# esd_project.net
KiCad netlist of a schematic drawn in Altium Designer
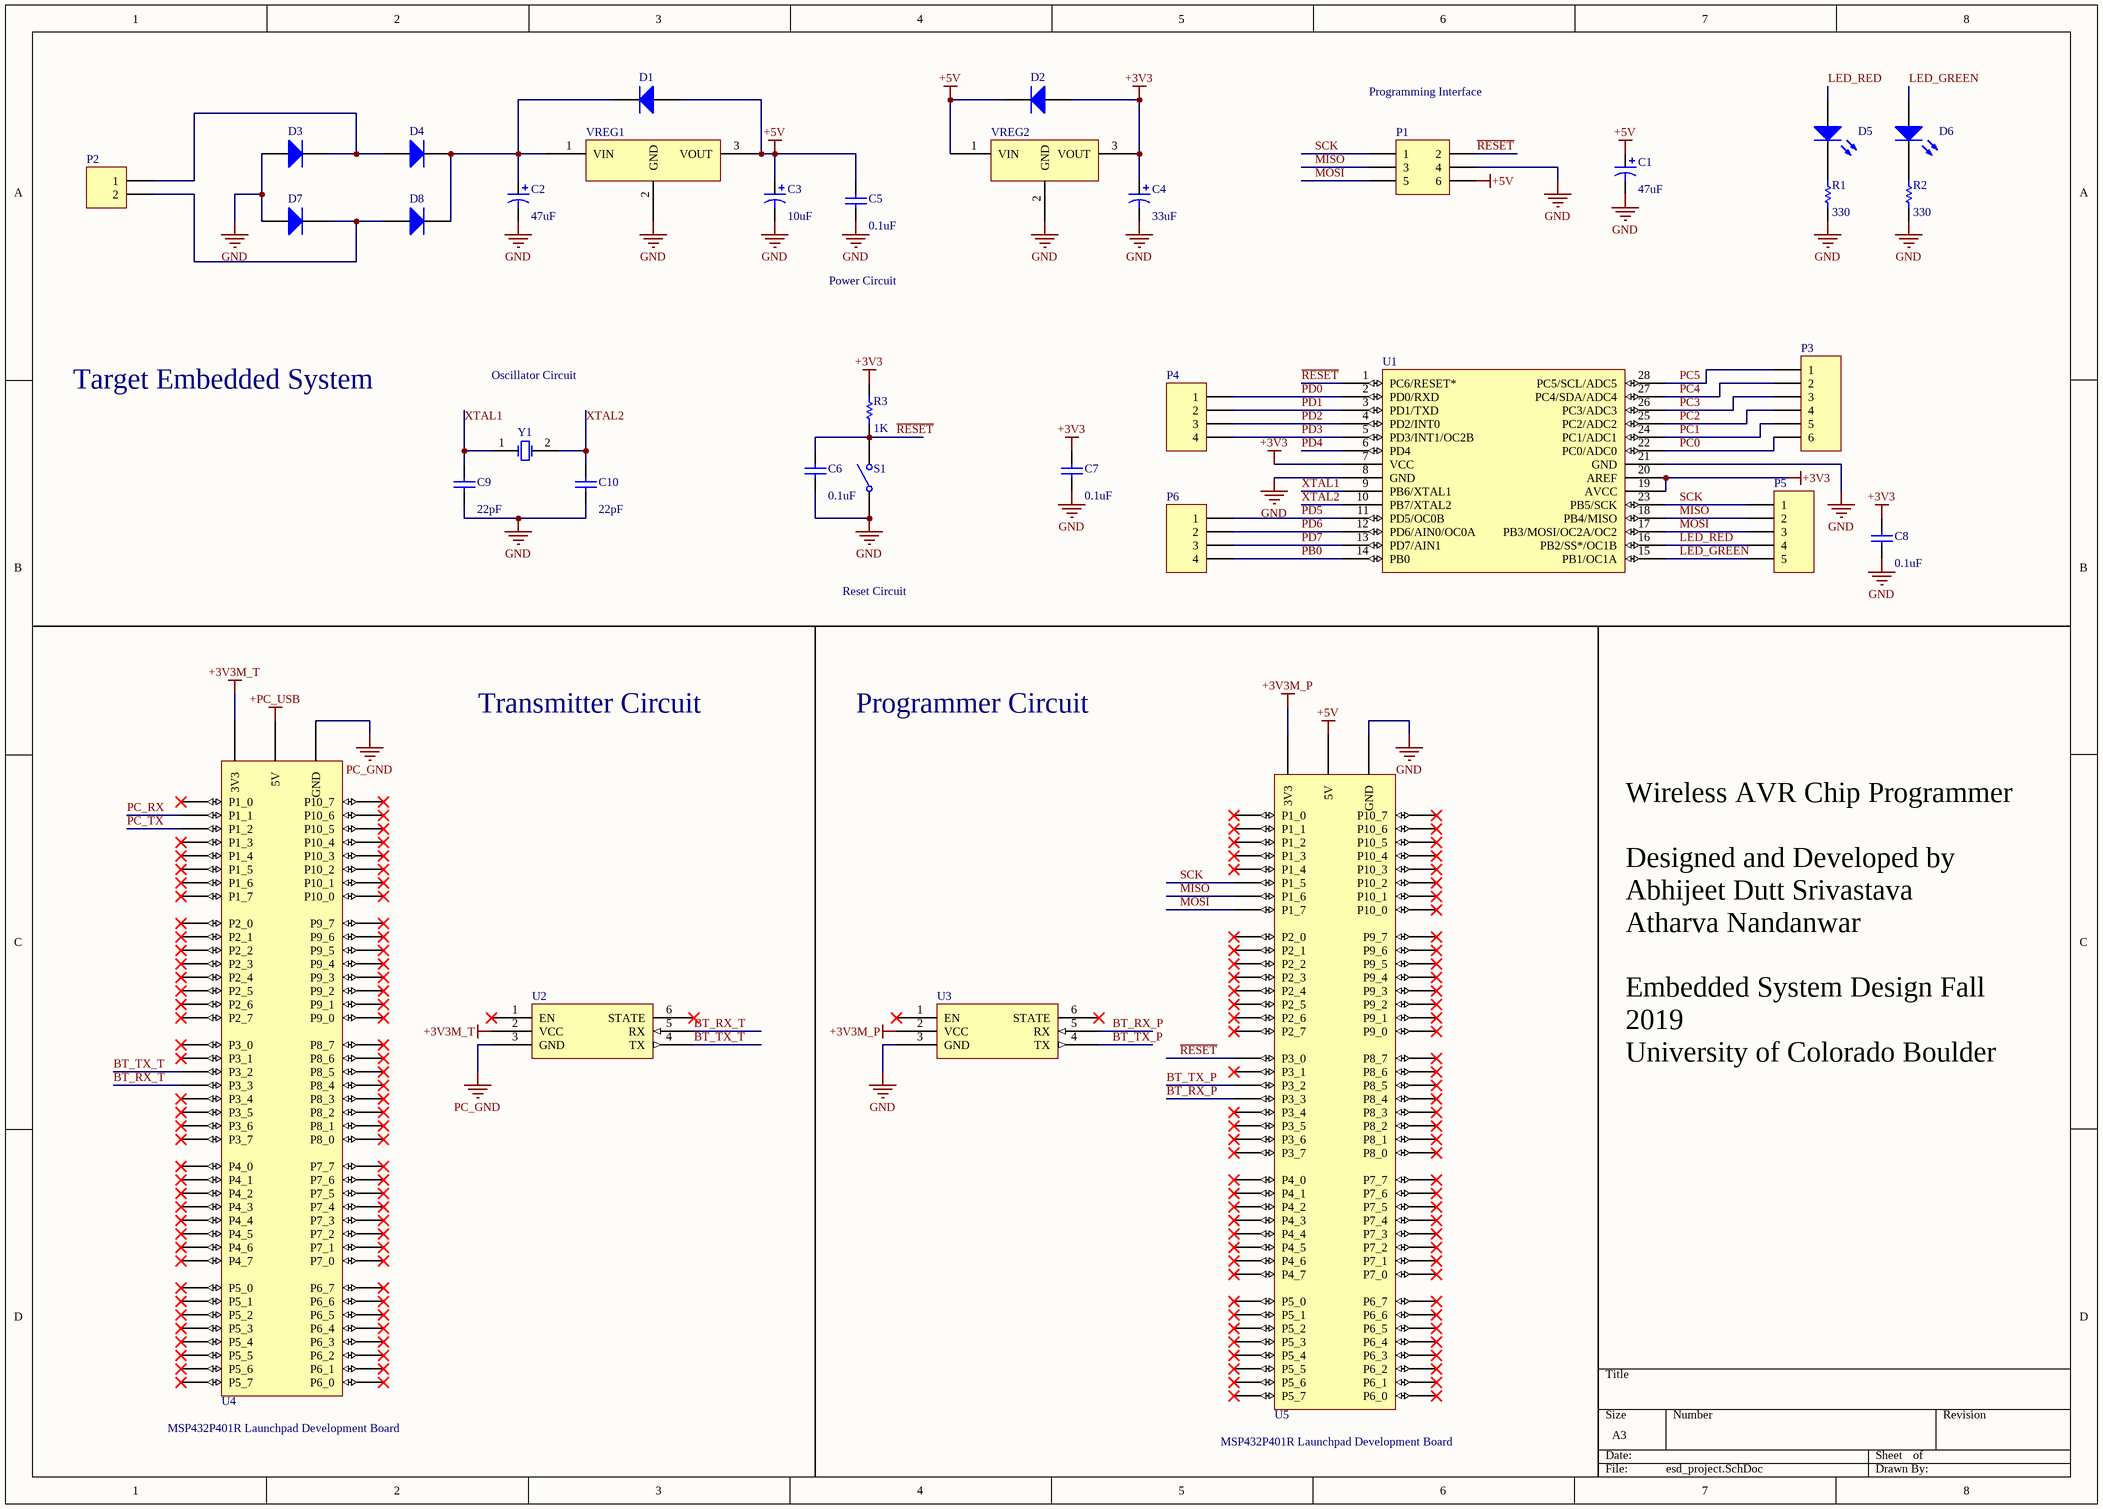
[diagram p0: esd_project.SchDoc]

(export (version "E")
  (design (tool "Eeschema 10.0.6"))
  (components
    (comp (ref "C1")
      (value "47uF")
      (footprint "RB7.6-15")
      (description "Polarized Capacitor (Radial)")
      (fields (field (name "Comment") "Cap Pol1") (field (name "PUBLISHER") "Altium Limited"))
      (libsource (lib "Miscellaneous Devices") (part "Cap Pol1"))
    )
    (comp (ref "C2")
      (value "47uF")
      (footprint "RB7.6-15")
      (description "Polarized Capacitor (Radial)")
      (fields (field (name "Comment") "Cap Pol1") (field (name "PUBLISHER") "Altium Limited"))
      (libsource (lib "Miscellaneous Devices") (part "Cap Pol1"))
    )
    (comp (ref "C3")
      (value "10uF")
      (footprint "RB7.6-15")
      (description "Polarized Capacitor (Radial)")
      (fields (field (name "Comment") "Cap Pol1") (field (name "PUBLISHER") "Altium Limited"))
      (libsource (lib "Miscellaneous Devices") (part "Cap Pol1"))
    )
    (comp (ref "C4")
      (value "33uF")
      (footprint "RB7.6-15")
      (description "Polarized Capacitor (Radial)")
      (fields (field (name "Comment") "Cap Pol1") (field (name "PUBLISHER") "Altium Limited"))
      (libsource (lib "Miscellaneous Devices") (part "Cap Pol1"))
    )
    (comp (ref "C5")
      (value "0.1uF")
      (footprint "RAD-0.3")
      (description "Capacitor")
      (fields (field (name "Comment") "Cap") (field (name "PUBLISHER") "Altium Limited"))
      (libsource (lib "Miscellaneous Devices") (part "Cap"))
    )
    (comp (ref "C6")
      (value "0.1uF")
      (footprint "RAD-0.3")
      (description "Capacitor")
      (fields (field (name "Comment") "Cap") (field (name "PUBLISHER") "Altium Limited"))
      (libsource (lib "Miscellaneous Devices") (part "Cap"))
    )
    (comp (ref "C7")
      (value "0.1uF")
      (footprint "RAD-0.3")
      (description "Capacitor")
      (fields (field (name "Comment") "Cap") (field (name "PUBLISHER") "Altium Limited"))
      (libsource (lib "Miscellaneous Devices") (part "Cap"))
    )
    (comp (ref "C8")
      (value "0.1uF")
      (footprint "RAD-0.3")
      (description "Capacitor")
      (fields (field (name "Comment") "Cap") (field (name "PUBLISHER") "Altium Limited"))
      (libsource (lib "Miscellaneous Devices") (part "Cap"))
    )
    (comp (ref "C9")
      (value "22pF")
      (footprint "RAD-0.3")
      (description "Capacitor")
      (fields (field (name "Comment") "Cap") (field (name "PUBLISHER") "Altium Limited"))
      (libsource (lib "Miscellaneous Devices") (part "Cap"))
    )
    (comp (ref "C10")
      (value "22pF")
      (footprint "RAD-0.3")
      (description "Capacitor")
      (fields (field (name "Comment") "Cap") (field (name "PUBLISHER") "Altium Limited"))
      (libsource (lib "Miscellaneous Devices") (part "Cap"))
    )
    (comp (ref "D1")
      (value "Diode 1N4003")
      (footprint "DO-41")
      (description "1 Amp General Purpose Rectifier")
      (fields (field (name "PUBLISHER") "Altium Limited"))
      (libsource (lib "Miscellaneous Devices") (part "Diode 1N4003"))
    )
    (comp (ref "D2")
      (value "Diode 1N4003")
      (footprint "DO-41")
      (description "1 Amp General Purpose Rectifier")
      (fields (field (name "PUBLISHER") "Altium Limited"))
      (libsource (lib "Miscellaneous Devices") (part "Diode 1N4003"))
    )
    (comp (ref "D3")
      (value "Diode 1N4003")
      (footprint "DO-41")
      (description "1 Amp General Purpose Rectifier")
      (fields (field (name "PUBLISHER") "Altium Limited"))
      (libsource (lib "Miscellaneous Devices") (part "Diode 1N4003"))
    )
    (comp (ref "D4")
      (value "Diode 1N4003")
      (footprint "DO-41")
      (description "1 Amp General Purpose Rectifier")
      (fields (field (name "PUBLISHER") "Altium Limited"))
      (libsource (lib "Miscellaneous Devices") (part "Diode 1N4003"))
    )
    (comp (ref "D5")
      (value "LED0")
      (footprint "LED-0")
      (description "Typical INFRARED GaAs LED")
      (fields (field (name "PUBLISHER") "Altium Limited"))
      (libsource (lib "Miscellaneous Devices") (part "LED0"))
    )
    (comp (ref "D6")
      (value "LED0")
      (footprint "LED-0")
      (description "Typical INFRARED GaAs LED")
      (fields (field (name "PUBLISHER") "Altium Limited"))
      (libsource (lib "Miscellaneous Devices") (part "LED0"))
    )
    (comp (ref "D7")
      (value "Diode 1N4003")
      (footprint "DO-41")
      (description "1 Amp General Purpose Rectifier")
      (fields (field (name "PUBLISHER") "Altium Limited"))
      (libsource (lib "Miscellaneous Devices") (part "Diode 1N4003"))
    )
    (comp (ref "D8")
      (value "Diode 1N4003")
      (footprint "DO-41")
      (description "1 Amp General Purpose Rectifier")
      (fields (field (name "PUBLISHER") "Altium Limited"))
      (libsource (lib "Miscellaneous Devices") (part "Diode 1N4003"))
    )
    (comp (ref "P1")
      (value "Header 3X2")
      (footprint "HDR2X3")
      (description "Header, 3-Pin, Dual row")
      (fields (field (name "PUBLISHER") "Altium Limited"))
      (libsource (lib "Miscellaneous Connectors") (part "Header 3X2"))
    )
    (comp (ref "P2")
      (value "MHDR1X2")
      (footprint "MHDR1X2")
      (description "Header, 2-Pin")
      (fields (field (name "PUBLISHER") "Altium Limited"))
      (libsource (lib "Miscellaneous Connectors") (part "MHDR1X2"))
    )
    (comp (ref "P3")
      (value "Header 6")
      (footprint "HDR1X6")
      (description "Header, 6-Pin")
      (fields (field (name "PUBLISHER") "Altium Limited"))
      (libsource (lib "Miscellaneous Connectors") (part "Header 6"))
    )
    (comp (ref "P4")
      (value "Header 4")
      (footprint "HDR1X4")
      (description "Header, 4-Pin")
      (fields (field (name "PUBLISHER") "Altium Limited"))
      (libsource (lib "Miscellaneous Connectors") (part "Header 4"))
    )
    (comp (ref "P5")
      (value "Header 5")
      (footprint "HDR1X5")
      (description "Header, 5-Pin")
      (fields (field (name "PUBLISHER") "Altium Limited"))
      (libsource (lib "Miscellaneous Connectors") (part "Header 5"))
    )
    (comp (ref "P6")
      (value "Header 4")
      (footprint "HDR1X4")
      (description "Header, 4-Pin")
      (fields (field (name "PUBLISHER") "Altium Limited"))
      (libsource (lib "Miscellaneous Connectors") (part "Header 4"))
    )
    (comp (ref "R1")
      (value "330")
      (footprint "AXIAL-0.3")
      (description "Resistor")
      (fields (field (name "Comment") "Res1") (field (name "PUBLISHER") "Altium Limited"))
      (libsource (lib "Miscellaneous Devices") (part "Res1"))
    )
    (comp (ref "R2")
      (value "330")
      (footprint "AXIAL-0.3")
      (description "Resistor")
      (fields (field (name "Comment") "Res1") (field (name "PUBLISHER") "Altium Limited"))
      (libsource (lib "Miscellaneous Devices") (part "Res1"))
    )
    (comp (ref "R3")
      (value "1K")
      (footprint "AXIAL-0.3")
      (description "Resistor")
      (fields (field (name "Comment") "Res1") (field (name "PUBLISHER") "Altium Limited"))
      (libsource (lib "Miscellaneous Devices") (part "Res1"))
    )
    (comp (ref "S1")
      (value "SW-SPST")
      (footprint "SPST-2")
      (description "Single-Pole, Single-Throw Switch")
      (fields (field (name "PUBLISHER") "Altium Limited"))
      (libsource (lib "Miscellaneous Devices") (part "SW-SPST"))
    )
    (comp (ref "U1")
      (value "ATmega328P-PU")
      (footprint "PDIP-28")
      (libsource (lib "esd_project") (part "ATmega328P-PU"))
    )
    (comp (ref "U2") (value "HC-05") (libsource (lib "esd_project") (part "HC-05")))
    (comp (ref "U3") (value "HC-05") (libsource (lib "esd_project") (part "HC-05")))
    (comp (ref "U4") (value "MSP432P401R") (libsource (lib "MSP432 DEV BOARD") (part "MSP432P401R")))
    (comp (ref "U5") (value "MSP432P401R") (libsource (lib "MSP432 DEV BOARD") (part "MSP432P401R")))
    (comp (ref "VREG1") (value "7805") (footprint "TO-220") (libsource (lib "esd_project") (part "7805")))
    (comp (ref "VREG2")
      (value "MCP1857")
      (footprint "SOT-223")
      (libsource (lib "esd_project") (part "AZ1117"))
    )
    (comp (ref "Y1")
      (value "8MHz")
      (footprint "R38")
      (description "Crystal Oscillator")
      (fields (field (name "PUBLISHER") "Altium Limited"))
      (libsource (lib "Miscellaneous Devices") (part "XTAL"))
    )
  )
  (nets
    (net (code "1") (name "+3V3") (class "Default")
      (node (ref "C4") (pin "1") (pinfunction "1_1") (pintype "passive"))
      (node (ref "C7") (pin "2") (pinfunction "2_2") (pintype "passive"))
      (node (ref "C8") (pin "2") (pinfunction "2_2") (pintype "passive"))
      (node (ref "D2") (pin "1") (pinfunction "A_1") (pintype "passive"))
      (node (ref "R3") (pin "2") (pinfunction "2_2") (pintype "passive"))
      (node (ref "U1") (pin "19") (pinfunction "AVCC_19") (pintype "power_in"))
      (node (ref "U1") (pin "20") (pinfunction "AREF_20") (pintype "power_in"))
      (node (ref "U1") (pin "7") (pinfunction "VCC_7") (pintype "power_in"))
      (node (ref "VREG2") (pin "3") (pinfunction "VOUT_3") (pintype "power_in"))
    )
    (net (code "2") (name "+3V3M_P") (class "Default")
      (node (ref "U3") (pin "2") (pinfunction "VCC_2") (pintype "power_in"))
      (node (ref "U5") (pin "1") (pinfunction "3V3_1") (pintype "power_in"))
    )
    (net (code "3") (name "+3V3M_T") (class "Default")
      (node (ref "U2") (pin "2") (pinfunction "VCC_2") (pintype "power_in"))
      (node (ref "U4") (pin "1") (pinfunction "3V3_1") (pintype "power_in"))
    )
    (net (code "4") (name "+5V") (class "Default")
      (node (ref "C1") (pin "1") (pinfunction "1_1") (pintype "passive"))
      (node (ref "C3") (pin "1") (pinfunction "1_1") (pintype "passive"))
      (node (ref "C5") (pin "1") (pinfunction "1_1") (pintype "passive"))
      (node (ref "D1") (pin "1") (pinfunction "A_1") (pintype "passive"))
      (node (ref "D2") (pin "2") (pinfunction "K_2") (pintype "passive"))
      (node (ref "P1") (pin "6") (pinfunction "6_6") (pintype "passive"))
      (node (ref "U5") (pin "82") (pinfunction "5V_82") (pintype "power_in"))
      (node (ref "VREG1") (pin "3") (pinfunction "VOUT_3") (pintype "power_in"))
      (node (ref "VREG2") (pin "1") (pinfunction "VIN_1") (pintype "power_in"))
    )
    (net (code "5") (name "+PC_USB") (class "Default")
      (node (ref "U4") (pin "82") (pinfunction "5V_82") (pintype "power_in"))
    )
    (net (code "6") (name "/BT_RX_P") (class "Default")
      (node (ref "U3") (pin "5") (pinfunction "RX_5") (pintype "input"))
      (node (ref "U5") (pin "21") (pinfunction "P3_3_21") (pintype "bidirectional"))
    )
    (net (code "7") (name "/BT_RX_T") (class "Default")
      (node (ref "U2") (pin "5") (pinfunction "RX_5") (pintype "input"))
      (node (ref "U4") (pin "21") (pinfunction "P3_3_21") (pintype "bidirectional"))
    )
    (net (code "8") (name "/BT_TX_P") (class "Default")
      (node (ref "U3") (pin "4") (pinfunction "TX_4") (pintype "output"))
      (node (ref "U5") (pin "20") (pinfunction "P3_2_20") (pintype "bidirectional"))
    )
    (net (code "9") (name "/BT_TX_T") (class "Default")
      (node (ref "U2") (pin "4") (pinfunction "TX_4") (pintype "output"))
      (node (ref "U4") (pin "20") (pinfunction "P3_2_20") (pintype "bidirectional"))
    )
    (net (code "10") (name "/LED_GREEN") (class "Default")
      (node (ref "D6") (pin "1") (pinfunction "A_1") (pintype "passive"))
      (node (ref "P5") (pin "5") (pinfunction "5_5") (pintype "passive"))
      (node (ref "U1") (pin "15") (pinfunction "PB1/OC1A_15") (pintype "bidirectional"))
    )
    (net (code "11") (name "/LED_RED") (class "Default")
      (node (ref "D5") (pin "1") (pinfunction "A_1") (pintype "passive"))
      (node (ref "P5") (pin "4") (pinfunction "4_4") (pintype "passive"))
      (node (ref "U1") (pin "16") (pinfunction "PB2/SS*/OC1B_16") (pintype "bidirectional"))
    )
    (net (code "12") (name "/MISO") (class "Default")
      (node (ref "P1") (pin "3") (pinfunction "3_3") (pintype "passive"))
      (node (ref "P5") (pin "2") (pinfunction "2_2") (pintype "passive"))
      (node (ref "U1") (pin "18") (pinfunction "PB4/MISO_18") (pintype "bidirectional"))
      (node (ref "U5") (pin "8") (pinfunction "P1_6_8") (pintype "bidirectional"))
    )
    (net (code "13") (name "/MOSI") (class "Default")
      (node (ref "P1") (pin "5") (pinfunction "5_5") (pintype "passive"))
      (node (ref "P5") (pin "3") (pinfunction "3_3") (pintype "passive"))
      (node (ref "U1") (pin "17") (pinfunction "PB3/MOSI/OC2A/OC2_17") (pintype "bidirectional"))
      (node (ref "U5") (pin "9") (pinfunction "P1_7_9") (pintype "bidirectional"))
    )
    (net (code "14") (name "/PB0") (class "Default")
      (node (ref "P6") (pin "4") (pinfunction "4_4") (pintype "passive"))
      (node (ref "U1") (pin "14") (pinfunction "PB0_14") (pintype "bidirectional"))
    )
    (net (code "15") (name "/PC0") (class "Default")
      (node (ref "P3") (pin "6") (pinfunction "6_6") (pintype "passive"))
      (node (ref "U1") (pin "22") (pinfunction "PC0/ADC0_22") (pintype "bidirectional"))
    )
    (net (code "16") (name "/PC1") (class "Default")
      (node (ref "P3") (pin "5") (pinfunction "5_5") (pintype "passive"))
      (node (ref "U1") (pin "24") (pinfunction "PC1/ADC1_24") (pintype "bidirectional"))
    )
    (net (code "17") (name "/PC2") (class "Default")
      (node (ref "P3") (pin "4") (pinfunction "4_4") (pintype "passive"))
      (node (ref "U1") (pin "25") (pinfunction "PC2/ADC2_25") (pintype "bidirectional"))
    )
    (net (code "18") (name "/PC3") (class "Default")
      (node (ref "P3") (pin "3") (pinfunction "3_3") (pintype "passive"))
      (node (ref "U1") (pin "26") (pinfunction "PC3/ADC3_26") (pintype "bidirectional"))
    )
    (net (code "19") (name "/PC4") (class "Default")
      (node (ref "P3") (pin "2") (pinfunction "2_2") (pintype "passive"))
      (node (ref "U1") (pin "27") (pinfunction "PC4/SDA/ADC4_27") (pintype "bidirectional"))
    )
    (net (code "20") (name "/PC5") (class "Default")
      (node (ref "P3") (pin "1") (pinfunction "1_1") (pintype "passive"))
      (node (ref "U1") (pin "28") (pinfunction "PC5/SCL/ADC5_28") (pintype "bidirectional"))
    )
    (net (code "21") (name "/PC_RX") (class "Default")
      (node (ref "U4") (pin "3") (pinfunction "P1_1_3") (pintype "bidirectional"))
    )
    (net (code "22") (name "/PC_TX") (class "Default")
      (node (ref "U4") (pin "4") (pinfunction "P1_2_4") (pintype "bidirectional"))
    )
    (net (code "23") (name "/PD0") (class "Default")
      (node (ref "P4") (pin "1") (pinfunction "1_1") (pintype "passive"))
      (node (ref "U1") (pin "2") (pinfunction "PD0/RXD_2") (pintype "bidirectional"))
    )
    (net (code "24") (name "/PD1") (class "Default")
      (node (ref "P4") (pin "2") (pinfunction "2_2") (pintype "passive"))
      (node (ref "U1") (pin "3") (pinfunction "PD1/TXD_3") (pintype "bidirectional"))
    )
    (net (code "25") (name "/PD2") (class "Default")
      (node (ref "P4") (pin "3") (pinfunction "3_3") (pintype "passive"))
      (node (ref "U1") (pin "4") (pinfunction "PD2/INT0_4") (pintype "bidirectional"))
    )
    (net (code "26") (name "/PD3") (class "Default")
      (node (ref "P4") (pin "4") (pinfunction "4_4") (pintype "passive"))
      (node (ref "U1") (pin "5") (pinfunction "PD3/INT1/OC2B_5") (pintype "bidirectional"))
    )
    (net (code "27") (name "/PD4") (class "Default")
      (node (ref "U1") (pin "6") (pinfunction "PD4_6") (pintype "bidirectional"))
    )
    (net (code "28") (name "/PD5") (class "Default")
      (node (ref "P6") (pin "1") (pinfunction "1_1") (pintype "passive"))
      (node (ref "U1") (pin "11") (pinfunction "PD5/OC0B_11") (pintype "bidirectional"))
    )
    (net (code "29") (name "/PD6") (class "Default")
      (node (ref "P6") (pin "2") (pinfunction "2_2") (pintype "passive"))
      (node (ref "U1") (pin "12") (pinfunction "PD6/AIN0/OC0A_12") (pintype "bidirectional"))
    )
    (net (code "30") (name "/PD7") (class "Default")
      (node (ref "P6") (pin "3") (pinfunction "3_3") (pintype "passive"))
      (node (ref "U1") (pin "13") (pinfunction "PD7/AIN1_13") (pintype "bidirectional"))
    )
    (net (code "31") (name "/SCK") (class "Default")
      (node (ref "P1") (pin "1") (pinfunction "1_1") (pintype "passive"))
      (node (ref "P5") (pin "1") (pinfunction "1_1") (pintype "passive"))
      (node (ref "U1") (pin "23") (pinfunction "PB5/SCK_23") (pintype "bidirectional"))
      (node (ref "U5") (pin "7") (pinfunction "P1_5_7") (pintype "bidirectional"))
    )
    (net (code "32") (name "/XTAL1") (class "Default")
      (node (ref "C9") (pin "2") (pinfunction "2_2") (pintype "passive"))
      (node (ref "U1") (pin "9") (pinfunction "PB6/XTAL1_9") (pintype "passive"))
      (node (ref "Y1") (pin "1") (pinfunction "OSC1_1") (pintype "passive"))
    )
    (net (code "33") (name "/XTAL2") (class "Default")
      (node (ref "C10") (pin "2") (pinfunction "2_2") (pintype "passive"))
      (node (ref "U1") (pin "10") (pinfunction "PB7/XTAL2_10") (pintype "passive"))
      (node (ref "Y1") (pin "2") (pinfunction "OSC2_2") (pintype "passive"))
    )
    (net (code "34") (name "/~{RESET}") (class "Default")
      (node (ref "C6") (pin "2") (pinfunction "2_2") (pintype "passive"))
      (node (ref "P1") (pin "2") (pinfunction "2_2") (pintype "passive"))
      (node (ref "R3") (pin "1") (pinfunction "1_1") (pintype "passive"))
      (node (ref "S1") (pin "2") (pinfunction "NO_2") (pintype "passive"))
      (node (ref "U1") (pin "1") (pinfunction "PC6/RESET*_1") (pintype "bidirectional"))
      (node (ref "U5") (pin "18") (pinfunction "P3_0_18") (pintype "bidirectional"))
    )
    (net (code "35") (name "GND") (class "Default")
      (node (ref "C1") (pin "2") (pinfunction "2_2") (pintype "passive"))
      (node (ref "C10") (pin "1") (pinfunction "1_1") (pintype "passive"))
      (node (ref "C2") (pin "2") (pinfunction "2_2") (pintype "passive"))
      (node (ref "C3") (pin "2") (pinfunction "2_2") (pintype "passive"))
      (node (ref "C4") (pin "2") (pinfunction "2_2") (pintype "passive"))
      (node (ref "C5") (pin "2") (pinfunction "2_2") (pintype "passive"))
      (node (ref "C6") (pin "1") (pinfunction "1_1") (pintype "passive"))
      (node (ref "C7") (pin "1") (pinfunction "1_1") (pintype "passive"))
      (node (ref "C8") (pin "1") (pinfunction "1_1") (pintype "passive"))
      (node (ref "C9") (pin "1") (pinfunction "1_1") (pintype "passive"))
      (node (ref "D3") (pin "1") (pinfunction "A_1") (pintype "passive"))
      (node (ref "D7") (pin "1") (pinfunction "A_1") (pintype "passive"))
      (node (ref "P1") (pin "4") (pinfunction "4_4") (pintype "passive"))
      (node (ref "R1") (pin "1") (pinfunction "1_1") (pintype "passive"))
      (node (ref "R2") (pin "1") (pinfunction "1_1") (pintype "passive"))
      (node (ref "S1") (pin "1") (pinfunction "COMMON_1") (pintype "passive"))
      (node (ref "U1") (pin "21") (pinfunction "GND_21") (pintype "power_in"))
      (node (ref "U1") (pin "8") (pinfunction "GND_8") (pintype "power_in"))
      (node (ref "U3") (pin "3") (pinfunction "GND_3") (pintype "power_in"))
      (node (ref "U5") (pin "83") (pinfunction "GND_83") (pintype "power_in"))
      (node (ref "VREG1") (pin "2") (pinfunction "GND_2") (pintype "passive"))
      (node (ref "VREG2") (pin "2") (pinfunction "GND_2") (pintype "power_in"))
    )
    (net (code "36") (name "Net-(D1-K)") (class "Default")
      (node (ref "C2") (pin "1") (pinfunction "1_1") (pintype "passive"))
      (node (ref "D1") (pin "2") (pinfunction "K_2") (pintype "passive"))
      (node (ref "D4") (pin "2") (pinfunction "K_2") (pintype "passive"))
      (node (ref "D8") (pin "2") (pinfunction "K_2") (pintype "passive"))
      (node (ref "VREG1") (pin "1") (pinfunction "VIN_1") (pintype "power_in"))
    )
    (net (code "37") (name "Net-(D3-K)") (class "Default")
      (node (ref "D3") (pin "2") (pinfunction "K_2") (pintype "passive"))
      (node (ref "D4") (pin "1") (pinfunction "A_1") (pintype "passive"))
      (node (ref "P2") (pin "1") (pinfunction "1_1") (pintype "passive"))
    )
    (net (code "38") (name "Net-(D5-K)") (class "Default")
      (node (ref "D5") (pin "2") (pinfunction "K_2") (pintype "passive"))
      (node (ref "R1") (pin "2") (pinfunction "2_2") (pintype "passive"))
    )
    (net (code "39") (name "Net-(D6-K)") (class "Default")
      (node (ref "D6") (pin "2") (pinfunction "K_2") (pintype "passive"))
      (node (ref "R2") (pin "2") (pinfunction "2_2") (pintype "passive"))
    )
    (net (code "40") (name "Net-(D7-K)") (class "Default")
      (node (ref "D7") (pin "2") (pinfunction "K_2") (pintype "passive"))
      (node (ref "D8") (pin "1") (pinfunction "A_1") (pintype "passive"))
      (node (ref "P2") (pin "2") (pinfunction "2_2") (pintype "passive"))
    )
    (net (code "41") (name "PC_GND") (class "Default")
      (node (ref "U2") (pin "3") (pinfunction "GND_3") (pintype "power_in"))
      (node (ref "U4") (pin "83") (pinfunction "GND_83") (pintype "power_in"))
    )
    (net (code "42") (name "unconnected-(U2-EN-Pad1)") (class "Default")
      (node (ref "U2") (pin "1") (pinfunction "EN_1") (pintype "power_in+no_connect"))
    )
    (net (code "43") (name "unconnected-(U2-STATE-Pad6)") (class "Default")
      (node (ref "U2") (pin "6") (pinfunction "STATE_6") (pintype "passive+no_connect"))
    )
    (net (code "44") (name "unconnected-(U3-EN-Pad1)") (class "Default")
      (node (ref "U3") (pin "1") (pinfunction "EN_1") (pintype "power_in+no_connect"))
    )
    (net (code "45") (name "unconnected-(U3-STATE-Pad6)") (class "Default")
      (node (ref "U3") (pin "6") (pinfunction "STATE_6") (pintype "passive+no_connect"))
    )
    (net (code "46") (name "unconnected-(U4-P1_0-Pad2)") (class "Default")
      (node (ref "U4") (pin "2") (pinfunction "P1_0_2") (pintype "bidirectional+no_connect"))
    )
    (net (code "47") (name "unconnected-(U4-P1_3-Pad5)") (class "Default")
      (node (ref "U4") (pin "5") (pinfunction "P1_3_5") (pintype "bidirectional+no_connect"))
    )
    (net (code "48") (name "unconnected-(U4-P1_4-Pad6)") (class "Default")
      (node (ref "U4") (pin "6") (pinfunction "P1_4_6") (pintype "bidirectional+no_connect"))
    )
    (net (code "49") (name "unconnected-(U4-P1_5-Pad7)") (class "Default")
      (node (ref "U4") (pin "7") (pinfunction "P1_5_7") (pintype "bidirectional+no_connect"))
    )
    (net (code "50") (name "unconnected-(U4-P1_6-Pad8)") (class "Default")
      (node (ref "U4") (pin "8") (pinfunction "P1_6_8") (pintype "bidirectional+no_connect"))
    )
    (net (code "51") (name "unconnected-(U4-P1_7-Pad9)") (class "Default")
      (node (ref "U4") (pin "9") (pinfunction "P1_7_9") (pintype "bidirectional+no_connect"))
    )
    (net (code "52") (name "unconnected-(U4-P2_0-Pad10)") (class "Default")
      (node (ref "U4") (pin "10") (pinfunction "P2_0_10") (pintype "bidirectional+no_connect"))
    )
    (net (code "53") (name "unconnected-(U4-P2_1-Pad11)") (class "Default")
      (node (ref "U4") (pin "11") (pinfunction "P2_1_11") (pintype "bidirectional+no_connect"))
    )
    (net (code "54") (name "unconnected-(U4-P2_2-Pad12)") (class "Default")
      (node (ref "U4") (pin "12") (pinfunction "P2_2_12") (pintype "bidirectional+no_connect"))
    )
    (net (code "55") (name "unconnected-(U4-P2_3-Pad13)") (class "Default")
      (node (ref "U4") (pin "13") (pinfunction "P2_3_13") (pintype "bidirectional+no_connect"))
    )
    (net (code "56") (name "unconnected-(U4-P2_4-Pad14)") (class "Default")
      (node (ref "U4") (pin "14") (pinfunction "P2_4_14") (pintype "bidirectional+no_connect"))
    )
    (net (code "57") (name "unconnected-(U4-P2_5-Pad15)") (class "Default")
      (node (ref "U4") (pin "15") (pinfunction "P2_5_15") (pintype "bidirectional+no_connect"))
    )
    (net (code "58") (name "unconnected-(U4-P2_6-Pad16)") (class "Default")
      (node (ref "U4") (pin "16") (pinfunction "P2_6_16") (pintype "bidirectional+no_connect"))
    )
    (net (code "59") (name "unconnected-(U4-P2_7-Pad17)") (class "Default")
      (node (ref "U4") (pin "17") (pinfunction "P2_7_17") (pintype "bidirectional+no_connect"))
    )
    (net (code "60") (name "unconnected-(U4-P3_0-Pad18)") (class "Default")
      (node (ref "U4") (pin "18") (pinfunction "P3_0_18") (pintype "bidirectional+no_connect"))
    )
    (net (code "61") (name "unconnected-(U4-P3_1-Pad19)") (class "Default")
      (node (ref "U4") (pin "19") (pinfunction "P3_1_19") (pintype "bidirectional+no_connect"))
    )
    (net (code "62") (name "unconnected-(U4-P3_4-Pad22)") (class "Default")
      (node (ref "U4") (pin "22") (pinfunction "P3_4_22") (pintype "bidirectional+no_connect"))
    )
    (net (code "63") (name "unconnected-(U4-P3_5-Pad23)") (class "Default")
      (node (ref "U4") (pin "23") (pinfunction "P3_5_23") (pintype "bidirectional+no_connect"))
    )
    (net (code "64") (name "unconnected-(U4-P3_6-Pad24)") (class "Default")
      (node (ref "U4") (pin "24") (pinfunction "P3_6_24") (pintype "bidirectional+no_connect"))
    )
    (net (code "65") (name "unconnected-(U4-P3_7-Pad25)") (class "Default")
      (node (ref "U4") (pin "25") (pinfunction "P3_7_25") (pintype "bidirectional+no_connect"))
    )
    (net (code "66") (name "unconnected-(U4-P4_0-Pad26)") (class "Default")
      (node (ref "U4") (pin "26") (pinfunction "P4_0_26") (pintype "bidirectional+no_connect"))
    )
    (net (code "67") (name "unconnected-(U4-P4_1-Pad27)") (class "Default")
      (node (ref "U4") (pin "27") (pinfunction "P4_1_27") (pintype "bidirectional+no_connect"))
    )
    (net (code "68") (name "unconnected-(U4-P4_2-Pad28)") (class "Default")
      (node (ref "U4") (pin "28") (pinfunction "P4_2_28") (pintype "bidirectional+no_connect"))
    )
    (net (code "69") (name "unconnected-(U4-P4_3-Pad29)") (class "Default")
      (node (ref "U4") (pin "29") (pinfunction "P4_3_29") (pintype "bidirectional+no_connect"))
    )
    (net (code "70") (name "unconnected-(U4-P4_4-Pad30)") (class "Default")
      (node (ref "U4") (pin "30") (pinfunction "P4_4_30") (pintype "bidirectional+no_connect"))
    )
    (net (code "71") (name "unconnected-(U4-P4_5-Pad31)") (class "Default")
      (node (ref "U4") (pin "31") (pinfunction "P4_5_31") (pintype "bidirectional+no_connect"))
    )
    (net (code "72") (name "unconnected-(U4-P4_6-Pad32)") (class "Default")
      (node (ref "U4") (pin "32") (pinfunction "P4_6_32") (pintype "bidirectional+no_connect"))
    )
    (net (code "73") (name "unconnected-(U4-P4_7-Pad33)") (class "Default")
      (node (ref "U4") (pin "33") (pinfunction "P4_7_33") (pintype "bidirectional+no_connect"))
    )
    (net (code "74") (name "unconnected-(U4-P5_0-Pad34)") (class "Default")
      (node (ref "U4") (pin "34") (pinfunction "P5_0_34") (pintype "bidirectional+no_connect"))
    )
    (net (code "75") (name "unconnected-(U4-P5_1-Pad35)") (class "Default")
      (node (ref "U4") (pin "35") (pinfunction "P5_1_35") (pintype "bidirectional+no_connect"))
    )
    (net (code "76") (name "unconnected-(U4-P5_2-Pad36)") (class "Default")
      (node (ref "U4") (pin "36") (pinfunction "P5_2_36") (pintype "bidirectional+no_connect"))
    )
    (net (code "77") (name "unconnected-(U4-P5_3-Pad37)") (class "Default")
      (node (ref "U4") (pin "37") (pinfunction "P5_3_37") (pintype "bidirectional+no_connect"))
    )
    (net (code "78") (name "unconnected-(U4-P5_4-Pad38)") (class "Default")
      (node (ref "U4") (pin "38") (pinfunction "P5_4_38") (pintype "bidirectional+no_connect"))
    )
    (net (code "79") (name "unconnected-(U4-P5_5-Pad39)") (class "Default")
      (node (ref "U4") (pin "39") (pinfunction "P5_5_39") (pintype "bidirectional+no_connect"))
    )
    (net (code "80") (name "unconnected-(U4-P5_6-Pad40)") (class "Default")
      (node (ref "U4") (pin "40") (pinfunction "P5_6_40") (pintype "bidirectional+no_connect"))
    )
    (net (code "81") (name "unconnected-(U4-P5_7-Pad41)") (class "Default")
      (node (ref "U4") (pin "41") (pinfunction "P5_7_41") (pintype "bidirectional+no_connect"))
    )
    (net (code "82") (name "unconnected-(U4-P6_0-Pad42)") (class "Default")
      (node (ref "U4") (pin "42") (pinfunction "P6_0_42") (pintype "bidirectional+no_connect"))
    )
    (net (code "83") (name "unconnected-(U4-P6_1-Pad43)") (class "Default")
      (node (ref "U4") (pin "43") (pinfunction "P6_1_43") (pintype "bidirectional+no_connect"))
    )
    (net (code "84") (name "unconnected-(U4-P6_2-Pad44)") (class "Default")
      (node (ref "U4") (pin "44") (pinfunction "P6_2_44") (pintype "bidirectional+no_connect"))
    )
    (net (code "85") (name "unconnected-(U4-P6_3-Pad45)") (class "Default")
      (node (ref "U4") (pin "45") (pinfunction "P6_3_45") (pintype "bidirectional+no_connect"))
    )
    (net (code "86") (name "unconnected-(U4-P6_4-Pad46)") (class "Default")
      (node (ref "U4") (pin "46") (pinfunction "P6_4_46") (pintype "bidirectional+no_connect"))
    )
    (net (code "87") (name "unconnected-(U4-P6_5-Pad47)") (class "Default")
      (node (ref "U4") (pin "47") (pinfunction "P6_5_47") (pintype "bidirectional+no_connect"))
    )
    (net (code "88") (name "unconnected-(U4-P6_6-Pad48)") (class "Default")
      (node (ref "U4") (pin "48") (pinfunction "P6_6_48") (pintype "bidirectional+no_connect"))
    )
    (net (code "89") (name "unconnected-(U4-P6_7-Pad49)") (class "Default")
      (node (ref "U4") (pin "49") (pinfunction "P6_7_49") (pintype "bidirectional+no_connect"))
    )
    (net (code "90") (name "unconnected-(U4-P7_0-Pad50)") (class "Default")
      (node (ref "U4") (pin "50") (pinfunction "P7_0_50") (pintype "bidirectional+no_connect"))
    )
    (net (code "91") (name "unconnected-(U4-P7_1-Pad51)") (class "Default")
      (node (ref "U4") (pin "51") (pinfunction "P7_1_51") (pintype "bidirectional+no_connect"))
    )
    (net (code "92") (name "unconnected-(U4-P7_2-Pad52)") (class "Default")
      (node (ref "U4") (pin "52") (pinfunction "P7_2_52") (pintype "bidirectional+no_connect"))
    )
    (net (code "93") (name "unconnected-(U4-P7_3-Pad53)") (class "Default")
      (node (ref "U4") (pin "53") (pinfunction "P7_3_53") (pintype "bidirectional+no_connect"))
    )
    (net (code "94") (name "unconnected-(U4-P7_4-Pad54)") (class "Default")
      (node (ref "U4") (pin "54") (pinfunction "P7_4_54") (pintype "bidirectional+no_connect"))
    )
    (net (code "95") (name "unconnected-(U4-P7_5-Pad55)") (class "Default")
      (node (ref "U4") (pin "55") (pinfunction "P7_5_55") (pintype "bidirectional+no_connect"))
    )
    (net (code "96") (name "unconnected-(U4-P7_6-Pad56)") (class "Default")
      (node (ref "U4") (pin "56") (pinfunction "P7_6_56") (pintype "bidirectional+no_connect"))
    )
    (net (code "97") (name "unconnected-(U4-P7_7-Pad57)") (class "Default")
      (node (ref "U4") (pin "57") (pinfunction "P7_7_57") (pintype "bidirectional+no_connect"))
    )
    (net (code "98") (name "unconnected-(U4-P8_0-Pad58)") (class "Default")
      (node (ref "U4") (pin "58") (pinfunction "P8_0_58") (pintype "bidirectional+no_connect"))
    )
    (net (code "99") (name "unconnected-(U4-P8_1-Pad59)") (class "Default")
      (node (ref "U4") (pin "59") (pinfunction "P8_1_59") (pintype "bidirectional+no_connect"))
    )
    (net (code "100") (name "unconnected-(U4-P8_2-Pad60)") (class "Default")
      (node (ref "U4") (pin "60") (pinfunction "P8_2_60") (pintype "bidirectional+no_connect"))
    )
    (net (code "101") (name "unconnected-(U4-P8_3-Pad61)") (class "Default")
      (node (ref "U4") (pin "61") (pinfunction "P8_3_61") (pintype "bidirectional+no_connect"))
    )
    (net (code "102") (name "unconnected-(U4-P8_4-Pad62)") (class "Default")
      (node (ref "U4") (pin "62") (pinfunction "P8_4_62") (pintype "bidirectional+no_connect"))
    )
    (net (code "103") (name "unconnected-(U4-P8_5-Pad63)") (class "Default")
      (node (ref "U4") (pin "63") (pinfunction "P8_5_63") (pintype "bidirectional+no_connect"))
    )
    (net (code "104") (name "unconnected-(U4-P8_6-Pad64)") (class "Default")
      (node (ref "U4") (pin "64") (pinfunction "P8_6_64") (pintype "bidirectional+no_connect"))
    )
    (net (code "105") (name "unconnected-(U4-P8_7-Pad65)") (class "Default")
      (node (ref "U4") (pin "65") (pinfunction "P8_7_65") (pintype "bidirectional+no_connect"))
    )
    (net (code "106") (name "unconnected-(U4-P9_0-Pad66)") (class "Default")
      (node (ref "U4") (pin "66") (pinfunction "P9_0_66") (pintype "bidirectional+no_connect"))
    )
    (net (code "107") (name "unconnected-(U4-P9_1-Pad67)") (class "Default")
      (node (ref "U4") (pin "67") (pinfunction "P9_1_67") (pintype "bidirectional+no_connect"))
    )
    (net (code "108") (name "unconnected-(U4-P9_2-Pad68)") (class "Default")
      (node (ref "U4") (pin "68") (pinfunction "P9_2_68") (pintype "bidirectional+no_connect"))
    )
    (net (code "109") (name "unconnected-(U4-P9_3-Pad69)") (class "Default")
      (node (ref "U4") (pin "69") (pinfunction "P9_3_69") (pintype "bidirectional+no_connect"))
    )
    (net (code "110") (name "unconnected-(U4-P9_4-Pad70)") (class "Default")
      (node (ref "U4") (pin "70") (pinfunction "P9_4_70") (pintype "bidirectional+no_connect"))
    )
    (net (code "111") (name "unconnected-(U4-P9_5-Pad71)") (class "Default")
      (node (ref "U4") (pin "71") (pinfunction "P9_5_71") (pintype "bidirectional+no_connect"))
    )
    (net (code "112") (name "unconnected-(U4-P9_6-Pad72)") (class "Default")
      (node (ref "U4") (pin "72") (pinfunction "P9_6_72") (pintype "bidirectional+no_connect"))
    )
    (net (code "113") (name "unconnected-(U4-P9_7-Pad73)") (class "Default")
      (node (ref "U4") (pin "73") (pinfunction "P9_7_73") (pintype "bidirectional+no_connect"))
    )
    (net (code "114") (name "unconnected-(U4-P10_0-Pad74)") (class "Default")
      (node (ref "U4") (pin "74") (pinfunction "P10_0_74") (pintype "bidirectional+no_connect"))
    )
    (net (code "115") (name "unconnected-(U4-P10_1-Pad75)") (class "Default")
      (node (ref "U4") (pin "75") (pinfunction "P10_1_75") (pintype "bidirectional+no_connect"))
    )
    (net (code "116") (name "unconnected-(U4-P10_2-Pad76)") (class "Default")
      (node (ref "U4") (pin "76") (pinfunction "P10_2_76") (pintype "bidirectional+no_connect"))
    )
    (net (code "117") (name "unconnected-(U4-P10_3-Pad77)") (class "Default")
      (node (ref "U4") (pin "77") (pinfunction "P10_3_77") (pintype "bidirectional+no_connect"))
    )
    (net (code "118") (name "unconnected-(U4-P10_4-Pad78)") (class "Default")
      (node (ref "U4") (pin "78") (pinfunction "P10_4_78") (pintype "bidirectional+no_connect"))
    )
    (net (code "119") (name "unconnected-(U4-P10_5-Pad79)") (class "Default")
      (node (ref "U4") (pin "79") (pinfunction "P10_5_79") (pintype "bidirectional+no_connect"))
    )
    (net (code "120") (name "unconnected-(U4-P10_6-Pad80)") (class "Default")
      (node (ref "U4") (pin "80") (pinfunction "P10_6_80") (pintype "bidirectional+no_connect"))
    )
    (net (code "121") (name "unconnected-(U4-P10_7-Pad81)") (class "Default")
      (node (ref "U4") (pin "81") (pinfunction "P10_7_81") (pintype "bidirectional+no_connect"))
    )
    (net (code "122") (name "unconnected-(U5-P1_0-Pad2)") (class "Default")
      (node (ref "U5") (pin "2") (pinfunction "P1_0_2") (pintype "bidirectional+no_connect"))
    )
    (net (code "123") (name "unconnected-(U5-P1_1-Pad3)") (class "Default")
      (node (ref "U5") (pin "3") (pinfunction "P1_1_3") (pintype "bidirectional+no_connect"))
    )
    (net (code "124") (name "unconnected-(U5-P1_2-Pad4)") (class "Default")
      (node (ref "U5") (pin "4") (pinfunction "P1_2_4") (pintype "bidirectional+no_connect"))
    )
    (net (code "125") (name "unconnected-(U5-P1_3-Pad5)") (class "Default")
      (node (ref "U5") (pin "5") (pinfunction "P1_3_5") (pintype "bidirectional+no_connect"))
    )
    (net (code "126") (name "unconnected-(U5-P1_4-Pad6)") (class "Default")
      (node (ref "U5") (pin "6") (pinfunction "P1_4_6") (pintype "bidirectional+no_connect"))
    )
    (net (code "127") (name "unconnected-(U5-P2_0-Pad10)") (class "Default")
      (node (ref "U5") (pin "10") (pinfunction "P2_0_10") (pintype "bidirectional+no_connect"))
    )
    (net (code "128") (name "unconnected-(U5-P2_1-Pad11)") (class "Default")
      (node (ref "U5") (pin "11") (pinfunction "P2_1_11") (pintype "bidirectional+no_connect"))
    )
    (net (code "129") (name "unconnected-(U5-P2_2-Pad12)") (class "Default")
      (node (ref "U5") (pin "12") (pinfunction "P2_2_12") (pintype "bidirectional+no_connect"))
    )
    (net (code "130") (name "unconnected-(U5-P2_3-Pad13)") (class "Default")
      (node (ref "U5") (pin "13") (pinfunction "P2_3_13") (pintype "bidirectional+no_connect"))
    )
    (net (code "131") (name "unconnected-(U5-P2_4-Pad14)") (class "Default")
      (node (ref "U5") (pin "14") (pinfunction "P2_4_14") (pintype "bidirectional+no_connect"))
    )
    (net (code "132") (name "unconnected-(U5-P2_5-Pad15)") (class "Default")
      (node (ref "U5") (pin "15") (pinfunction "P2_5_15") (pintype "bidirectional+no_connect"))
    )
    (net (code "133") (name "unconnected-(U5-P2_6-Pad16)") (class "Default")
      (node (ref "U5") (pin "16") (pinfunction "P2_6_16") (pintype "bidirectional+no_connect"))
    )
    (net (code "134") (name "unconnected-(U5-P2_7-Pad17)") (class "Default")
      (node (ref "U5") (pin "17") (pinfunction "P2_7_17") (pintype "bidirectional+no_connect"))
    )
    (net (code "135") (name "unconnected-(U5-P3_1-Pad19)") (class "Default")
      (node (ref "U5") (pin "19") (pinfunction "P3_1_19") (pintype "bidirectional+no_connect"))
    )
    (net (code "136") (name "unconnected-(U5-P3_4-Pad22)") (class "Default")
      (node (ref "U5") (pin "22") (pinfunction "P3_4_22") (pintype "bidirectional+no_connect"))
    )
    (net (code "137") (name "unconnected-(U5-P3_5-Pad23)") (class "Default")
      (node (ref "U5") (pin "23") (pinfunction "P3_5_23") (pintype "bidirectional+no_connect"))
    )
    (net (code "138") (name "unconnected-(U5-P3_6-Pad24)") (class "Default")
      (node (ref "U5") (pin "24") (pinfunction "P3_6_24") (pintype "bidirectional+no_connect"))
    )
    (net (code "139") (name "unconnected-(U5-P3_7-Pad25)") (class "Default")
      (node (ref "U5") (pin "25") (pinfunction "P3_7_25") (pintype "bidirectional+no_connect"))
    )
    (net (code "140") (name "unconnected-(U5-P4_0-Pad26)") (class "Default")
      (node (ref "U5") (pin "26") (pinfunction "P4_0_26") (pintype "bidirectional+no_connect"))
    )
    (net (code "141") (name "unconnected-(U5-P4_1-Pad27)") (class "Default")
      (node (ref "U5") (pin "27") (pinfunction "P4_1_27") (pintype "bidirectional+no_connect"))
    )
    (net (code "142") (name "unconnected-(U5-P4_2-Pad28)") (class "Default")
      (node (ref "U5") (pin "28") (pinfunction "P4_2_28") (pintype "bidirectional+no_connect"))
    )
    (net (code "143") (name "unconnected-(U5-P4_3-Pad29)") (class "Default")
      (node (ref "U5") (pin "29") (pinfunction "P4_3_29") (pintype "bidirectional+no_connect"))
    )
    (net (code "144") (name "unconnected-(U5-P4_4-Pad30)") (class "Default")
      (node (ref "U5") (pin "30") (pinfunction "P4_4_30") (pintype "bidirectional+no_connect"))
    )
    (net (code "145") (name "unconnected-(U5-P4_5-Pad31)") (class "Default")
      (node (ref "U5") (pin "31") (pinfunction "P4_5_31") (pintype "bidirectional+no_connect"))
    )
    (net (code "146") (name "unconnected-(U5-P4_6-Pad32)") (class "Default")
      (node (ref "U5") (pin "32") (pinfunction "P4_6_32") (pintype "bidirectional+no_connect"))
    )
    (net (code "147") (name "unconnected-(U5-P4_7-Pad33)") (class "Default")
      (node (ref "U5") (pin "33") (pinfunction "P4_7_33") (pintype "bidirectional+no_connect"))
    )
    (net (code "148") (name "unconnected-(U5-P5_0-Pad34)") (class "Default")
      (node (ref "U5") (pin "34") (pinfunction "P5_0_34") (pintype "bidirectional+no_connect"))
    )
    (net (code "149") (name "unconnected-(U5-P5_1-Pad35)") (class "Default")
      (node (ref "U5") (pin "35") (pinfunction "P5_1_35") (pintype "bidirectional+no_connect"))
    )
    (net (code "150") (name "unconnected-(U5-P5_2-Pad36)") (class "Default")
      (node (ref "U5") (pin "36") (pinfunction "P5_2_36") (pintype "bidirectional+no_connect"))
    )
    (net (code "151") (name "unconnected-(U5-P5_3-Pad37)") (class "Default")
      (node (ref "U5") (pin "37") (pinfunction "P5_3_37") (pintype "bidirectional+no_connect"))
    )
    (net (code "152") (name "unconnected-(U5-P5_4-Pad38)") (class "Default")
      (node (ref "U5") (pin "38") (pinfunction "P5_4_38") (pintype "bidirectional+no_connect"))
    )
    (net (code "153") (name "unconnected-(U5-P5_5-Pad39)") (class "Default")
      (node (ref "U5") (pin "39") (pinfunction "P5_5_39") (pintype "bidirectional+no_connect"))
    )
    (net (code "154") (name "unconnected-(U5-P5_6-Pad40)") (class "Default")
      (node (ref "U5") (pin "40") (pinfunction "P5_6_40") (pintype "bidirectional+no_connect"))
    )
    (net (code "155") (name "unconnected-(U5-P5_7-Pad41)") (class "Default")
      (node (ref "U5") (pin "41") (pinfunction "P5_7_41") (pintype "bidirectional+no_connect"))
    )
    (net (code "156") (name "unconnected-(U5-P6_0-Pad42)") (class "Default")
      (node (ref "U5") (pin "42") (pinfunction "P6_0_42") (pintype "bidirectional+no_connect"))
    )
    (net (code "157") (name "unconnected-(U5-P6_1-Pad43)") (class "Default")
      (node (ref "U5") (pin "43") (pinfunction "P6_1_43") (pintype "bidirectional+no_connect"))
    )
    (net (code "158") (name "unconnected-(U5-P6_2-Pad44)") (class "Default")
      (node (ref "U5") (pin "44") (pinfunction "P6_2_44") (pintype "bidirectional+no_connect"))
    )
    (net (code "159") (name "unconnected-(U5-P6_3-Pad45)") (class "Default")
      (node (ref "U5") (pin "45") (pinfunction "P6_3_45") (pintype "bidirectional+no_connect"))
    )
    (net (code "160") (name "unconnected-(U5-P6_4-Pad46)") (class "Default")
      (node (ref "U5") (pin "46") (pinfunction "P6_4_46") (pintype "bidirectional+no_connect"))
    )
    (net (code "161") (name "unconnected-(U5-P6_5-Pad47)") (class "Default")
      (node (ref "U5") (pin "47") (pinfunction "P6_5_47") (pintype "bidirectional+no_connect"))
    )
    (net (code "162") (name "unconnected-(U5-P6_6-Pad48)") (class "Default")
      (node (ref "U5") (pin "48") (pinfunction "P6_6_48") (pintype "bidirectional+no_connect"))
    )
    (net (code "163") (name "unconnected-(U5-P6_7-Pad49)") (class "Default")
      (node (ref "U5") (pin "49") (pinfunction "P6_7_49") (pintype "bidirectional+no_connect"))
    )
    (net (code "164") (name "unconnected-(U5-P7_0-Pad50)") (class "Default")
      (node (ref "U5") (pin "50") (pinfunction "P7_0_50") (pintype "bidirectional+no_connect"))
    )
    (net (code "165") (name "unconnected-(U5-P7_1-Pad51)") (class "Default")
      (node (ref "U5") (pin "51") (pinfunction "P7_1_51") (pintype "bidirectional+no_connect"))
    )
    (net (code "166") (name "unconnected-(U5-P7_2-Pad52)") (class "Default")
      (node (ref "U5") (pin "52") (pinfunction "P7_2_52") (pintype "bidirectional+no_connect"))
    )
    (net (code "167") (name "unconnected-(U5-P7_3-Pad53)") (class "Default")
      (node (ref "U5") (pin "53") (pinfunction "P7_3_53") (pintype "bidirectional+no_connect"))
    )
    (net (code "168") (name "unconnected-(U5-P7_4-Pad54)") (class "Default")
      (node (ref "U5") (pin "54") (pinfunction "P7_4_54") (pintype "bidirectional+no_connect"))
    )
    (net (code "169") (name "unconnected-(U5-P7_5-Pad55)") (class "Default")
      (node (ref "U5") (pin "55") (pinfunction "P7_5_55") (pintype "bidirectional+no_connect"))
    )
    (net (code "170") (name "unconnected-(U5-P7_6-Pad56)") (class "Default")
      (node (ref "U5") (pin "56") (pinfunction "P7_6_56") (pintype "bidirectional+no_connect"))
    )
    (net (code "171") (name "unconnected-(U5-P7_7-Pad57)") (class "Default")
      (node (ref "U5") (pin "57") (pinfunction "P7_7_57") (pintype "bidirectional+no_connect"))
    )
    (net (code "172") (name "unconnected-(U5-P8_0-Pad58)") (class "Default")
      (node (ref "U5") (pin "58") (pinfunction "P8_0_58") (pintype "bidirectional+no_connect"))
    )
    (net (code "173") (name "unconnected-(U5-P8_1-Pad59)") (class "Default")
      (node (ref "U5") (pin "59") (pinfunction "P8_1_59") (pintype "bidirectional+no_connect"))
    )
    (net (code "174") (name "unconnected-(U5-P8_2-Pad60)") (class "Default")
      (node (ref "U5") (pin "60") (pinfunction "P8_2_60") (pintype "bidirectional+no_connect"))
    )
    (net (code "175") (name "unconnected-(U5-P8_3-Pad61)") (class "Default")
      (node (ref "U5") (pin "61") (pinfunction "P8_3_61") (pintype "bidirectional+no_connect"))
    )
    (net (code "176") (name "unconnected-(U5-P8_4-Pad62)") (class "Default")
      (node (ref "U5") (pin "62") (pinfunction "P8_4_62") (pintype "bidirectional+no_connect"))
    )
    (net (code "177") (name "unconnected-(U5-P8_5-Pad63)") (class "Default")
      (node (ref "U5") (pin "63") (pinfunction "P8_5_63") (pintype "bidirectional+no_connect"))
    )
    (net (code "178") (name "unconnected-(U5-P8_6-Pad64)") (class "Default")
      (node (ref "U5") (pin "64") (pinfunction "P8_6_64") (pintype "bidirectional+no_connect"))
    )
    (net (code "179") (name "unconnected-(U5-P8_7-Pad65)") (class "Default")
      (node (ref "U5") (pin "65") (pinfunction "P8_7_65") (pintype "bidirectional+no_connect"))
    )
    (net (code "180") (name "unconnected-(U5-P9_0-Pad66)") (class "Default")
      (node (ref "U5") (pin "66") (pinfunction "P9_0_66") (pintype "bidirectional+no_connect"))
    )
    (net (code "181") (name "unconnected-(U5-P9_1-Pad67)") (class "Default")
      (node (ref "U5") (pin "67") (pinfunction "P9_1_67") (pintype "bidirectional+no_connect"))
    )
    (net (code "182") (name "unconnected-(U5-P9_2-Pad68)") (class "Default")
      (node (ref "U5") (pin "68") (pinfunction "P9_2_68") (pintype "bidirectional+no_connect"))
    )
    (net (code "183") (name "unconnected-(U5-P9_3-Pad69)") (class "Default")
      (node (ref "U5") (pin "69") (pinfunction "P9_3_69") (pintype "bidirectional+no_connect"))
    )
    (net (code "184") (name "unconnected-(U5-P9_4-Pad70)") (class "Default")
      (node (ref "U5") (pin "70") (pinfunction "P9_4_70") (pintype "bidirectional+no_connect"))
    )
    (net (code "185") (name "unconnected-(U5-P9_5-Pad71)") (class "Default")
      (node (ref "U5") (pin "71") (pinfunction "P9_5_71") (pintype "bidirectional+no_connect"))
    )
    (net (code "186") (name "unconnected-(U5-P9_6-Pad72)") (class "Default")
      (node (ref "U5") (pin "72") (pinfunction "P9_6_72") (pintype "bidirectional+no_connect"))
    )
    (net (code "187") (name "unconnected-(U5-P9_7-Pad73)") (class "Default")
      (node (ref "U5") (pin "73") (pinfunction "P9_7_73") (pintype "bidirectional+no_connect"))
    )
    (net (code "188") (name "unconnected-(U5-P10_0-Pad74)") (class "Default")
      (node (ref "U5") (pin "74") (pinfunction "P10_0_74") (pintype "bidirectional+no_connect"))
    )
    (net (code "189") (name "unconnected-(U5-P10_1-Pad75)") (class "Default")
      (node (ref "U5") (pin "75") (pinfunction "P10_1_75") (pintype "bidirectional+no_connect"))
    )
    (net (code "190") (name "unconnected-(U5-P10_2-Pad76)") (class "Default")
      (node (ref "U5") (pin "76") (pinfunction "P10_2_76") (pintype "bidirectional+no_connect"))
    )
    (net (code "191") (name "unconnected-(U5-P10_3-Pad77)") (class "Default")
      (node (ref "U5") (pin "77") (pinfunction "P10_3_77") (pintype "bidirectional+no_connect"))
    )
    (net (code "192") (name "unconnected-(U5-P10_4-Pad78)") (class "Default")
      (node (ref "U5") (pin "78") (pinfunction "P10_4_78") (pintype "bidirectional+no_connect"))
    )
    (net (code "193") (name "unconnected-(U5-P10_5-Pad79)") (class "Default")
      (node (ref "U5") (pin "79") (pinfunction "P10_5_79") (pintype "bidirectional+no_connect"))
    )
    (net (code "194") (name "unconnected-(U5-P10_6-Pad80)") (class "Default")
      (node (ref "U5") (pin "80") (pinfunction "P10_6_80") (pintype "bidirectional+no_connect"))
    )
    (net (code "195") (name "unconnected-(U5-P10_7-Pad81)") (class "Default")
      (node (ref "U5") (pin "81") (pinfunction "P10_7_81") (pintype "bidirectional+no_connect"))
    )
  )
)
